# Chess_MOD.net
KiCad netlist of a schematic drawn in EAGLE
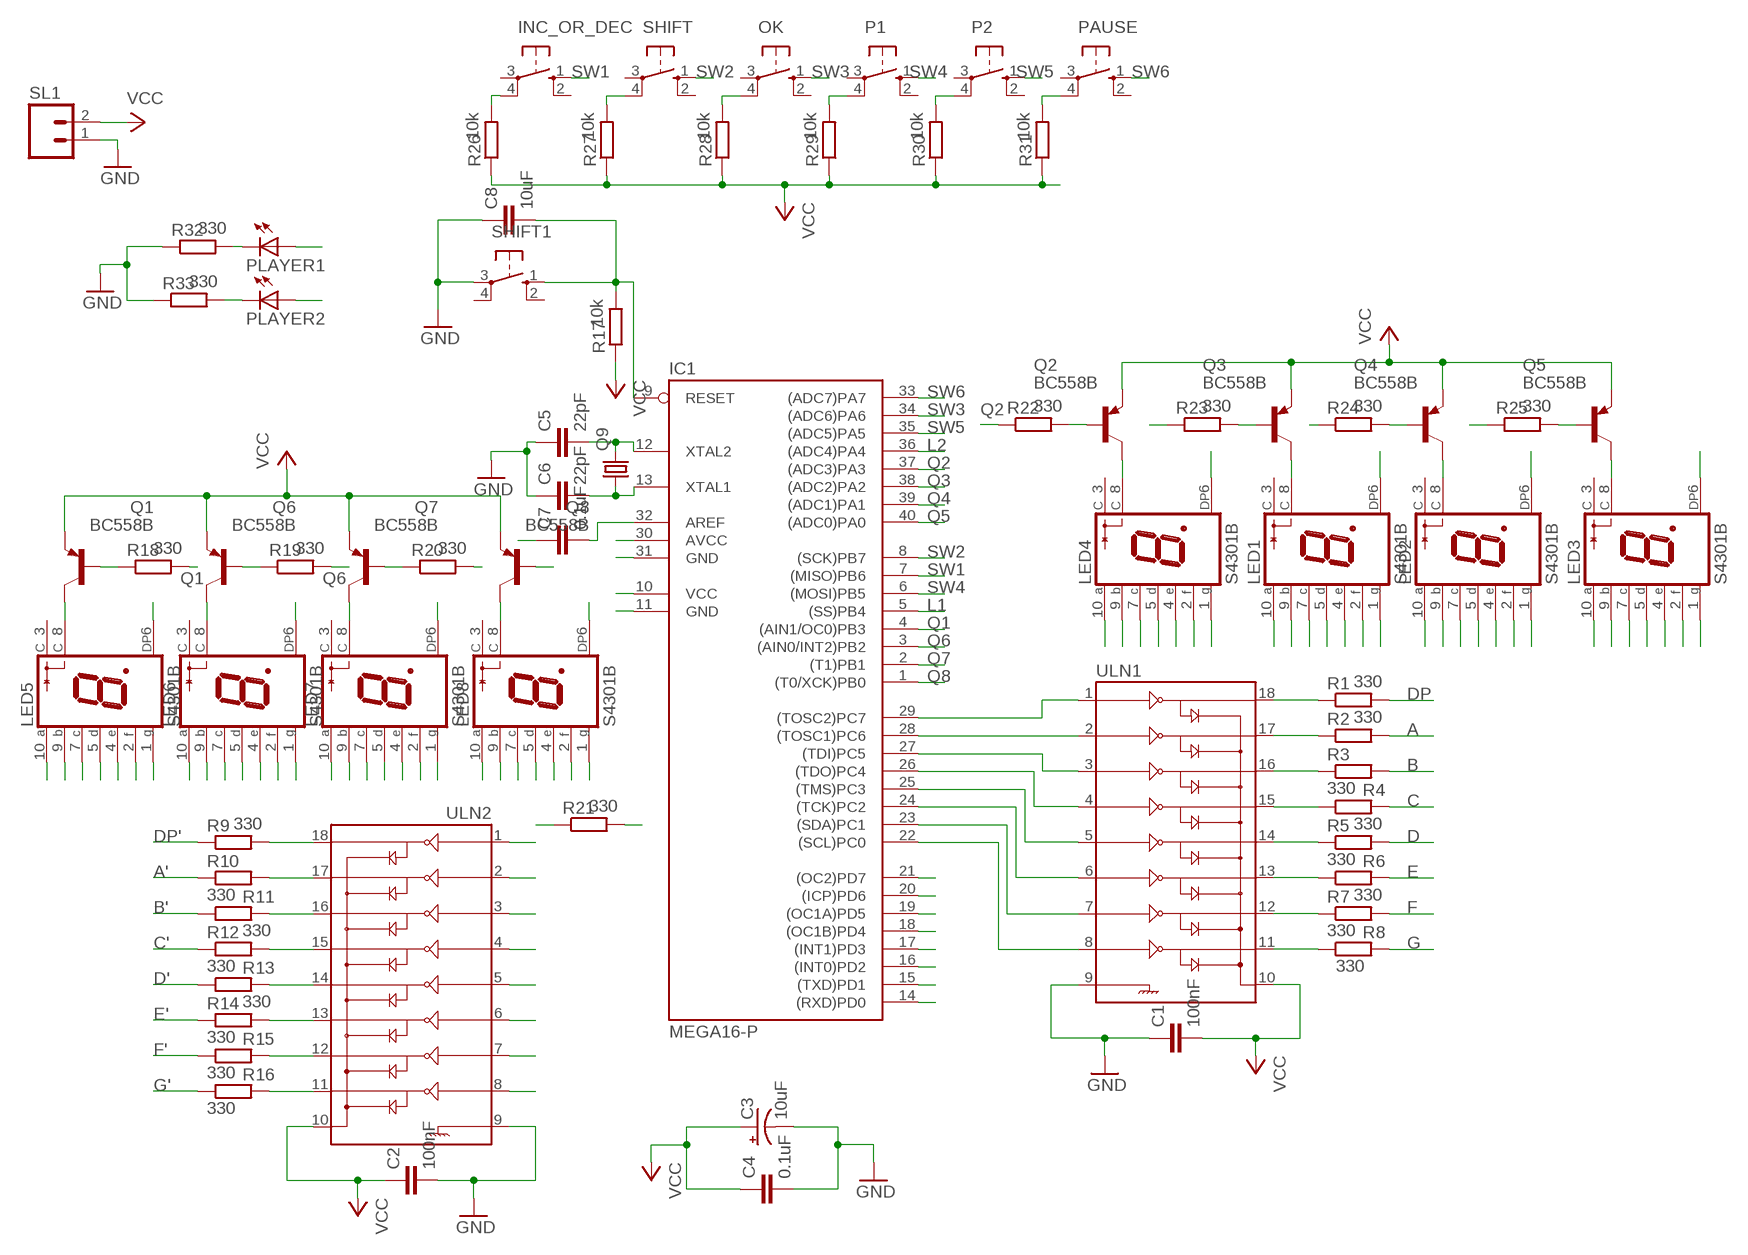
[diagram p0: schematic, sheet 1]

(export (version "E")
  (design (tool "Eeschema 10.0.6"))
  (components
    (comp (ref "C1")
      (value "100nF")
      (footprint "eagle-import:C025-024X044")
      (libsource (lib "eagle-import") (part "C-EU025-024X044"))
    )
    (comp (ref "C2")
      (value "100nF")
      (footprint "eagle-import:C025-024X044")
      (libsource (lib "eagle-import") (part "C-EU025-024X044"))
    )
    (comp (ref "C3")
      (value "10uF")
      (footprint "eagle-import:E2,5-7")
      (libsource (lib "eagle-import") (part "CPOL-USE2.5-7"))
    )
    (comp (ref "C4")
      (value "0.1uF")
      (footprint "eagle-import:C025-024X044")
      (libsource (lib "eagle-import") (part "C-EU025-024X044"))
    )
    (comp (ref "C5")
      (value "22pF")
      (footprint "eagle-import:C025-024X044")
      (libsource (lib "eagle-import") (part "C-EU025-024X044"))
    )
    (comp (ref "C6")
      (value "22pF")
      (footprint "eagle-import:C025-024X044")
      (libsource (lib "eagle-import") (part "C-EU025-024X044"))
    )
    (comp (ref "C7")
      (value "0.1uF")
      (footprint "eagle-import:C025-024X044")
      (libsource (lib "eagle-import") (part "C-EU025-024X044"))
    )
    (comp (ref "C8")
      (value "10uF")
      (footprint "eagle-import:C025-024X044")
      (libsource (lib "eagle-import") (part "C-EU025-024X044"))
    )
    (comp (ref "IC1")
      (value "MEGA16-P")
      (footprint "eagle-import:DIL40")
      (fields (field (name "MPN") "ATMEGA16-16PU"))
      (libsource (lib "eagle-import") (part "MEGA16-P"))
    )
    (comp (ref "INC_OR_DEC")
      (value "10-XX")
      (footprint "eagle-import:B3F-10XX")
      (fields (field (name "MPN") "B3F-1000"))
      (libsource (lib "eagle-import") (part "10-XX"))
    )
    (comp (ref "LED1")
      (value "S4301B")
      (footprint "eagle-import:S4301B")
      (libsource (lib "eagle-import") (part "S4301B"))
    )
    (comp (ref "LED2")
      (value "S4301B")
      (footprint "eagle-import:S4301B")
      (libsource (lib "eagle-import") (part "S4301B"))
    )
    (comp (ref "LED3")
      (value "S4301B")
      (footprint "eagle-import:S4301B")
      (libsource (lib "eagle-import") (part "S4301B"))
    )
    (comp (ref "LED4")
      (value "S4301B")
      (footprint "eagle-import:S4301B")
      (libsource (lib "eagle-import") (part "S4301B"))
    )
    (comp (ref "LED5")
      (value "S4301B")
      (footprint "eagle-import:S4301B")
      (libsource (lib "eagle-import") (part "S4301B"))
    )
    (comp (ref "LED6")
      (value "S4301B")
      (footprint "eagle-import:S4301B")
      (libsource (lib "eagle-import") (part "S4301B"))
    )
    (comp (ref "LED7")
      (value "S4301B")
      (footprint "eagle-import:S4301B")
      (libsource (lib "eagle-import") (part "S4301B"))
    )
    (comp (ref "LED8")
      (value "S4301B")
      (footprint "eagle-import:S4301B")
      (libsource (lib "eagle-import") (part "S4301B"))
    )
    (comp (ref "OK")
      (value "10-XX")
      (footprint "eagle-import:B3F-10XX")
      (fields (field (name "MPN") "B3F-1000"))
      (libsource (lib "eagle-import") (part "10-XX"))
    )
    (comp (ref "P1")
      (value "10-XX")
      (footprint "eagle-import:B3F-10XX")
      (fields (field (name "MPN") "B3F-1000"))
      (libsource (lib "eagle-import") (part "10-XX"))
    )
    (comp (ref "P2")
      (value "10-XX")
      (footprint "eagle-import:B3F-10XX")
      (fields (field (name "MPN") "B3F-1000"))
      (libsource (lib "eagle-import") (part "10-XX"))
    )
    (comp (ref "PAUSE")
      (value "10-XX")
      (footprint "eagle-import:B3F-10XX")
      (fields (field (name "MPN") "B3F-1000"))
      (libsource (lib "eagle-import") (part "10-XX"))
    )
    (comp (ref "PLAYER1")
      (value "LED5MM")
      (footprint "eagle-import:LED5MM")
      (libsource (lib "eagle-import") (part "LED5MM"))
    )
    (comp (ref "PLAYER2")
      (value "LED5MM")
      (footprint "eagle-import:LED5MM")
      (libsource (lib "eagle-import") (part "LED5MM"))
    )
    (comp (ref "Q1")
      (value "BC558B")
      (footprint "eagle-import:TO92-EBC")
      (libsource (lib "eagle-import") (part "BC558B"))
    )
    (comp (ref "Q2")
      (value "BC558B")
      (footprint "eagle-import:TO92-EBC")
      (libsource (lib "eagle-import") (part "BC558B"))
    )
    (comp (ref "Q3")
      (value "BC558B")
      (footprint "eagle-import:TO92-EBC")
      (libsource (lib "eagle-import") (part "BC558B"))
    )
    (comp (ref "Q4")
      (value "BC558B")
      (footprint "eagle-import:TO92-EBC")
      (libsource (lib "eagle-import") (part "BC558B"))
    )
    (comp (ref "Q5")
      (value "BC558B")
      (footprint "eagle-import:TO92-EBC")
      (libsource (lib "eagle-import") (part "BC558B"))
    )
    (comp (ref "Q6")
      (value "BC558B")
      (footprint "eagle-import:TO92-EBC")
      (libsource (lib "eagle-import") (part "BC558B"))
    )
    (comp (ref "Q7")
      (value "BC558B")
      (footprint "eagle-import:TO92-EBC")
      (libsource (lib "eagle-import") (part "BC558B"))
    )
    (comp (ref "Q8")
      (value "BC558B")
      (footprint "eagle-import:TO92-EBC")
      (libsource (lib "eagle-import") (part "BC558B"))
    )
    (comp (ref "Q9")
      (value "CRYSTALHC49US")
      (footprint "eagle-import:HC49US")
      (libsource (lib "eagle-import") (part "CRYSTALHC49US"))
    )
    (comp (ref "R1")
      (value "330")
      (footprint "eagle-import:0204_7")
      (libsource (lib "eagle-import") (part "R-EU_0204/7"))
    )
    (comp (ref "R2")
      (value "330")
      (footprint "eagle-import:0204_7")
      (libsource (lib "eagle-import") (part "R-EU_0204/7"))
    )
    (comp (ref "R3")
      (value "330")
      (footprint "eagle-import:0204_7")
      (libsource (lib "eagle-import") (part "R-EU_0204/7"))
    )
    (comp (ref "R4")
      (value "330")
      (footprint "eagle-import:0204_7")
      (libsource (lib "eagle-import") (part "R-EU_0204/7"))
    )
    (comp (ref "R5")
      (value "330")
      (footprint "eagle-import:0204_7")
      (libsource (lib "eagle-import") (part "R-EU_0204/7"))
    )
    (comp (ref "R6")
      (value "330")
      (footprint "eagle-import:0204_7")
      (libsource (lib "eagle-import") (part "R-EU_0204/7"))
    )
    (comp (ref "R7")
      (value "330")
      (footprint "eagle-import:0204_7")
      (libsource (lib "eagle-import") (part "R-EU_0204/7"))
    )
    (comp (ref "R8")
      (value "330")
      (footprint "eagle-import:0204_7")
      (libsource (lib "eagle-import") (part "R-EU_0204/7"))
    )
    (comp (ref "R9")
      (value "330")
      (footprint "eagle-import:0204_7")
      (libsource (lib "eagle-import") (part "R-EU_0204/7"))
    )
    (comp (ref "R10")
      (value "330")
      (footprint "eagle-import:0204_7")
      (libsource (lib "eagle-import") (part "R-EU_0204/7"))
    )
    (comp (ref "R11")
      (value "330")
      (footprint "eagle-import:0204_7")
      (libsource (lib "eagle-import") (part "R-EU_0204/7"))
    )
    (comp (ref "R12")
      (value "330")
      (footprint "eagle-import:0204_7")
      (libsource (lib "eagle-import") (part "R-EU_0204/7"))
    )
    (comp (ref "R13")
      (value "330")
      (footprint "eagle-import:0204_7")
      (libsource (lib "eagle-import") (part "R-EU_0204/7"))
    )
    (comp (ref "R14")
      (value "330")
      (footprint "eagle-import:0204_7")
      (libsource (lib "eagle-import") (part "R-EU_0204/7"))
    )
    (comp (ref "R15")
      (value "330")
      (footprint "eagle-import:0204_7")
      (libsource (lib "eagle-import") (part "R-EU_0204/7"))
    )
    (comp (ref "R16")
      (value "330")
      (footprint "eagle-import:0204_7")
      (libsource (lib "eagle-import") (part "R-EU_0204/7"))
    )
    (comp (ref "R17")
      (value "10k")
      (footprint "eagle-import:0204_7")
      (libsource (lib "eagle-import") (part "R-EU_0204/7"))
    )
    (comp (ref "R18")
      (value "330")
      (footprint "eagle-import:0204_7")
      (libsource (lib "eagle-import") (part "R-EU_0204/7"))
    )
    (comp (ref "R19")
      (value "330")
      (footprint "eagle-import:0204_7")
      (libsource (lib "eagle-import") (part "R-EU_0204/7"))
    )
    (comp (ref "R20")
      (value "330")
      (footprint "eagle-import:0204_7")
      (libsource (lib "eagle-import") (part "R-EU_0204/7"))
    )
    (comp (ref "R21")
      (value "330")
      (footprint "eagle-import:0204_7")
      (libsource (lib "eagle-import") (part "R-EU_0204/7"))
    )
    (comp (ref "R22")
      (value "330")
      (footprint "eagle-import:0204_7")
      (libsource (lib "eagle-import") (part "R-EU_0204/7"))
    )
    (comp (ref "R23")
      (value "330")
      (footprint "eagle-import:0204_7")
      (libsource (lib "eagle-import") (part "R-EU_0204/7"))
    )
    (comp (ref "R24")
      (value "330")
      (footprint "eagle-import:0204_7")
      (libsource (lib "eagle-import") (part "R-EU_0204/7"))
    )
    (comp (ref "R25")
      (value "330")
      (footprint "eagle-import:0204_7")
      (libsource (lib "eagle-import") (part "R-EU_0204/7"))
    )
    (comp (ref "R26")
      (value "10k")
      (footprint "eagle-import:0204_7")
      (libsource (lib "eagle-import") (part "R-EU_0204/7"))
    )
    (comp (ref "R27")
      (value "10k")
      (footprint "eagle-import:0204_7")
      (libsource (lib "eagle-import") (part "R-EU_0204/7"))
    )
    (comp (ref "R28")
      (value "10k")
      (footprint "eagle-import:0204_7")
      (libsource (lib "eagle-import") (part "R-EU_0204/7"))
    )
    (comp (ref "R29")
      (value "10k")
      (footprint "eagle-import:0204_7")
      (libsource (lib "eagle-import") (part "R-EU_0204/7"))
    )
    (comp (ref "R30")
      (value "10k")
      (footprint "eagle-import:0204_7")
      (libsource (lib "eagle-import") (part "R-EU_0204/7"))
    )
    (comp (ref "R31")
      (value "10k")
      (footprint "eagle-import:0204_7")
      (libsource (lib "eagle-import") (part "R-EU_0204/7"))
    )
    (comp (ref "R32")
      (value "330")
      (footprint "eagle-import:0204_7")
      (libsource (lib "eagle-import") (part "R-EU_0204/7"))
    )
    (comp (ref "R33")
      (value "330")
      (footprint "eagle-import:0204_7")
      (libsource (lib "eagle-import") (part "R-EU_0204/7"))
    )
    (comp (ref "SHIFT")
      (value "10-XX")
      (footprint "eagle-import:B3F-10XX")
      (fields (field (name "MPN") "B3F-1000"))
      (libsource (lib "eagle-import") (part "10-XX"))
    )
    (comp (ref "SHIFT1")
      (value "10-XX")
      (footprint "eagle-import:B3F-10XX")
      (fields (field (name "MPN") "B3F-1000"))
      (libsource (lib "eagle-import") (part "10-XX"))
    )
    (comp (ref "SL1")
      (value "M02")
      (footprint "eagle-import:02P")
      (libsource (lib "eagle-import") (part "M02"))
    )
    (comp (ref "ULN1")
      (value "ULN2803DIP")
      (footprint "eagle-import:DIL18")
      (libsource (lib "eagle-import") (part "ULN2803DIP"))
    )
    (comp (ref "ULN2")
      (value "ULN2803DIP")
      (footprint "eagle-import:DIL18")
      (libsource (lib "eagle-import") (part "ULN2803DIP"))
    )
  )
  (nets
    (net (code "1") (name "/1") (class "Default")
      (node (ref "IC1") (pin "21") (pinfunction "(OC2)PD7_21") (pintype "bidirectional"))
      (node (ref "ULN2") (pin "1") (pinfunction "1_1") (pintype "bidirectional"))
    )
    (net (code "2") (name "/2") (class "Default")
      (node (ref "IC1") (pin "20") (pinfunction "(ICP)PD6_20") (pintype "bidirectional"))
      (node (ref "ULN2") (pin "2") (pinfunction "2_2") (pintype "bidirectional"))
    )
    (net (code "3") (name "/3") (class "Default")
      (node (ref "IC1") (pin "19") (pinfunction "(OC1A)PD5_19") (pintype "bidirectional"))
      (node (ref "ULN2") (pin "3") (pinfunction "3_3") (pintype "bidirectional"))
    )
    (net (code "4") (name "/4") (class "Default")
      (node (ref "IC1") (pin "18") (pinfunction "(OC1B)PD4_18") (pintype "bidirectional"))
      (node (ref "ULN2") (pin "4") (pinfunction "4_4") (pintype "bidirectional"))
    )
    (net (code "5") (name "/5") (class "Default")
      (node (ref "IC1") (pin "17") (pinfunction "(INT1)PD3_17") (pintype "bidirectional"))
      (node (ref "ULN2") (pin "5") (pinfunction "5_5") (pintype "bidirectional"))
    )
    (net (code "6") (name "/6") (class "Default")
      (node (ref "IC1") (pin "16") (pinfunction "(INT0)PD2_16") (pintype "bidirectional"))
      (node (ref "ULN2") (pin "6") (pinfunction "6_6") (pintype "bidirectional"))
    )
    (net (code "7") (name "/7") (class "Default")
      (node (ref "IC1") (pin "15") (pinfunction "(TXD)PD1_15") (pintype "bidirectional"))
      (node (ref "ULN2") (pin "7") (pinfunction "7_7") (pintype "bidirectional"))
    )
    (net (code "8") (name "/8") (class "Default")
      (node (ref "IC1") (pin "14") (pinfunction "(RXD)PD0_14") (pintype "bidirectional"))
      (node (ref "ULN2") (pin "8") (pinfunction "8_8") (pintype "bidirectional"))
    )
    (net (code "9") (name "/A") (class "Default")
      (node (ref "LED1") (pin "10") (pinfunction "A_10") (pintype "passive"))
      (node (ref "LED2") (pin "10") (pinfunction "A_10") (pintype "passive"))
      (node (ref "LED3") (pin "10") (pinfunction "A_10") (pintype "passive"))
      (node (ref "LED4") (pin "10") (pinfunction "A_10") (pintype "passive"))
      (node (ref "R2") (pin "2") (pinfunction "2_2") (pintype "passive"))
    )
    (net (code "10") (name "/A'") (class "Default")
      (node (ref "LED5") (pin "10") (pinfunction "A_10") (pintype "passive"))
      (node (ref "LED6") (pin "10") (pinfunction "A_10") (pintype "passive"))
      (node (ref "LED7") (pin "10") (pinfunction "A_10") (pintype "passive"))
      (node (ref "LED8") (pin "10") (pinfunction "A_10") (pintype "passive"))
      (node (ref "R10") (pin "1") (pinfunction "1_1") (pintype "passive"))
    )
    (net (code "11") (name "/B") (class "Default")
      (node (ref "LED1") (pin "9") (pinfunction "B_9") (pintype "passive"))
      (node (ref "LED2") (pin "9") (pinfunction "B_9") (pintype "passive"))
      (node (ref "LED3") (pin "9") (pinfunction "B_9") (pintype "passive"))
      (node (ref "LED4") (pin "9") (pinfunction "B_9") (pintype "passive"))
      (node (ref "R3") (pin "2") (pinfunction "2_2") (pintype "passive"))
    )
    (net (code "12") (name "/B'") (class "Default")
      (node (ref "LED5") (pin "9") (pinfunction "B_9") (pintype "passive"))
      (node (ref "LED6") (pin "9") (pinfunction "B_9") (pintype "passive"))
      (node (ref "LED7") (pin "9") (pinfunction "B_9") (pintype "passive"))
      (node (ref "LED8") (pin "9") (pinfunction "B_9") (pintype "passive"))
      (node (ref "R11") (pin "1") (pinfunction "1_1") (pintype "passive"))
    )
    (net (code "13") (name "/C") (class "Default")
      (node (ref "LED1") (pin "7") (pinfunction "C_7") (pintype "passive"))
      (node (ref "LED2") (pin "7") (pinfunction "C_7") (pintype "passive"))
      (node (ref "LED3") (pin "7") (pinfunction "C_7") (pintype "passive"))
      (node (ref "LED4") (pin "7") (pinfunction "C_7") (pintype "passive"))
      (node (ref "R4") (pin "2") (pinfunction "2_2") (pintype "passive"))
    )
    (net (code "14") (name "/C'") (class "Default")
      (node (ref "LED5") (pin "7") (pinfunction "C_7") (pintype "passive"))
      (node (ref "LED6") (pin "7") (pinfunction "C_7") (pintype "passive"))
      (node (ref "LED7") (pin "7") (pinfunction "C_7") (pintype "passive"))
      (node (ref "LED8") (pin "7") (pinfunction "C_7") (pintype "passive"))
      (node (ref "R12") (pin "1") (pinfunction "1_1") (pintype "passive"))
    )
    (net (code "15") (name "/D") (class "Default")
      (node (ref "LED1") (pin "5") (pinfunction "D_5") (pintype "passive"))
      (node (ref "LED2") (pin "5") (pinfunction "D_5") (pintype "passive"))
      (node (ref "LED3") (pin "5") (pinfunction "D_5") (pintype "passive"))
      (node (ref "LED4") (pin "5") (pinfunction "D_5") (pintype "passive"))
      (node (ref "R5") (pin "2") (pinfunction "2_2") (pintype "passive"))
    )
    (net (code "16") (name "/D'") (class "Default")
      (node (ref "LED5") (pin "5") (pinfunction "D_5") (pintype "passive"))
      (node (ref "LED6") (pin "5") (pinfunction "D_5") (pintype "passive"))
      (node (ref "LED7") (pin "5") (pinfunction "D_5") (pintype "passive"))
      (node (ref "LED8") (pin "5") (pinfunction "D_5") (pintype "passive"))
      (node (ref "R13") (pin "1") (pinfunction "1_1") (pintype "passive"))
    )
    (net (code "17") (name "/DP") (class "Default")
      (node (ref "LED1") (pin "6") (pinfunction "DP_6") (pintype "passive"))
      (node (ref "LED2") (pin "6") (pinfunction "DP_6") (pintype "passive"))
      (node (ref "LED3") (pin "6") (pinfunction "DP_6") (pintype "passive"))
      (node (ref "LED4") (pin "6") (pinfunction "DP_6") (pintype "passive"))
      (node (ref "R1") (pin "2") (pinfunction "2_2") (pintype "passive"))
    )
    (net (code "18") (name "/DP'") (class "Default")
      (node (ref "LED5") (pin "6") (pinfunction "DP_6") (pintype "passive"))
      (node (ref "LED6") (pin "6") (pinfunction "DP_6") (pintype "passive"))
      (node (ref "LED7") (pin "6") (pinfunction "DP_6") (pintype "passive"))
      (node (ref "LED8") (pin "6") (pinfunction "DP_6") (pintype "passive"))
      (node (ref "R9") (pin "1") (pinfunction "1_1") (pintype "passive"))
    )
    (net (code "19") (name "/E") (class "Default")
      (node (ref "LED2") (pin "4") (pinfunction "E_4") (pintype "passive"))
      (node (ref "LED3") (pin "4") (pinfunction "E_4") (pintype "passive"))
      (node (ref "LED4") (pin "4") (pinfunction "E_4") (pintype "passive"))
      (node (ref "R6") (pin "2") (pinfunction "2_2") (pintype "passive"))
    )
    (net (code "20") (name "/E'") (class "Default")
      (node (ref "LED5") (pin "4") (pinfunction "E_4") (pintype "passive"))
      (node (ref "LED6") (pin "4") (pinfunction "E_4") (pintype "passive"))
      (node (ref "LED7") (pin "4") (pinfunction "E_4") (pintype "passive"))
      (node (ref "LED8") (pin "4") (pinfunction "E_4") (pintype "passive"))
      (node (ref "R14") (pin "1") (pinfunction "1_1") (pintype "passive"))
    )
    (net (code "21") (name "/F") (class "Default")
      (node (ref "LED1") (pin "2") (pinfunction "F_2") (pintype "passive"))
      (node (ref "LED2") (pin "2") (pinfunction "F_2") (pintype "passive"))
      (node (ref "LED3") (pin "2") (pinfunction "F_2") (pintype "passive"))
      (node (ref "LED4") (pin "2") (pinfunction "F_2") (pintype "passive"))
      (node (ref "R7") (pin "2") (pinfunction "2_2") (pintype "passive"))
    )
    (net (code "22") (name "/F'") (class "Default")
      (node (ref "LED5") (pin "2") (pinfunction "F_2") (pintype "passive"))
      (node (ref "LED6") (pin "2") (pinfunction "F_2") (pintype "passive"))
      (node (ref "LED7") (pin "2") (pinfunction "F_2") (pintype "passive"))
      (node (ref "LED8") (pin "2") (pinfunction "F_2") (pintype "passive"))
      (node (ref "R15") (pin "1") (pinfunction "1_1") (pintype "passive"))
    )
    (net (code "23") (name "/G") (class "Default")
      (node (ref "LED1") (pin "1") (pinfunction "G_1") (pintype "passive"))
      (node (ref "LED2") (pin "1") (pinfunction "G_1") (pintype "passive"))
      (node (ref "LED3") (pin "1") (pinfunction "G_1") (pintype "passive"))
      (node (ref "LED4") (pin "1") (pinfunction "G_1") (pintype "passive"))
      (node (ref "R8") (pin "2") (pinfunction "2_2") (pintype "passive"))
    )
    (net (code "24") (name "/G'") (class "Default")
      (node (ref "LED5") (pin "1") (pinfunction "G_1") (pintype "passive"))
      (node (ref "LED6") (pin "1") (pinfunction "G_1") (pintype "passive"))
      (node (ref "LED7") (pin "1") (pinfunction "G_1") (pintype "passive"))
      (node (ref "LED8") (pin "1") (pinfunction "G_1") (pintype "passive"))
      (node (ref "R16") (pin "1") (pinfunction "1_1") (pintype "passive"))
    )
    (net (code "25") (name "/L1") (class "Default")
      (node (ref "IC1") (pin "5") (pinfunction "(SS)PB4_5") (pintype "bidirectional"))
      (node (ref "PLAYER1") (pin "A") (pinfunction "A_A") (pintype "passive"))
    )
    (net (code "26") (name "/L2") (class "Default")
      (node (ref "IC1") (pin "36") (pinfunction "(ADC4)PA4_36") (pintype "bidirectional"))
      (node (ref "PLAYER2") (pin "A") (pinfunction "A_A") (pintype "passive"))
    )
    (net (code "27") (name "/Q1") (class "Default")
      (node (ref "IC1") (pin "4") (pinfunction "(AIN1/OC0)PB3_4") (pintype "bidirectional"))
      (node (ref "R18") (pin "2") (pinfunction "2_2") (pintype "passive"))
    )
    (net (code "28") (name "/Q2") (class "Default")
      (node (ref "IC1") (pin "37") (pinfunction "(ADC3)PA3_37") (pintype "bidirectional"))
      (node (ref "R22") (pin "1") (pinfunction "1_1") (pintype "passive"))
    )
    (net (code "29") (name "/Q3") (class "Default")
      (node (ref "IC1") (pin "38") (pinfunction "(ADC2)PA2_38") (pintype "bidirectional"))
      (node (ref "R23") (pin "1") (pinfunction "1_1") (pintype "passive"))
    )
    (net (code "30") (name "/Q4") (class "Default")
      (node (ref "IC1") (pin "39") (pinfunction "(ADC1)PA1_39") (pintype "bidirectional"))
      (node (ref "R24") (pin "1") (pinfunction "1_1") (pintype "passive"))
    )
    (net (code "31") (name "/Q5") (class "Default")
      (node (ref "IC1") (pin "40") (pinfunction "(ADC0)PA0_40") (pintype "bidirectional"))
      (node (ref "R25") (pin "1") (pinfunction "1_1") (pintype "passive"))
    )
    (net (code "32") (name "/Q6") (class "Default")
      (node (ref "IC1") (pin "3") (pinfunction "(AIN0/INT2)PB2_3") (pintype "bidirectional"))
      (node (ref "R19") (pin "2") (pinfunction "2_2") (pintype "passive"))
    )
    (net (code "33") (name "/Q7") (class "Default")
      (node (ref "IC1") (pin "2") (pinfunction "(T1)PB1_2") (pintype "bidirectional"))
      (node (ref "R20") (pin "2") (pinfunction "2_2") (pintype "passive"))
    )
    (net (code "34") (name "/Q8") (class "Default")
      (node (ref "IC1") (pin "1") (pinfunction "(T0/XCK)PB0_1") (pintype "bidirectional"))
      (node (ref "R21") (pin "2") (pinfunction "2_2") (pintype "passive"))
    )
    (net (code "35") (name "/SW1") (class "Default")
      (node (ref "IC1") (pin "7") (pinfunction "(MISO)PB6_7") (pintype "bidirectional"))
      (node (ref "INC_OR_DEC") (pin "1") (pinfunction "S_1") (pintype "passive"))
    )
    (net (code "36") (name "/SW2") (class "Default")
      (node (ref "IC1") (pin "8") (pinfunction "(SCK)PB7_8") (pintype "bidirectional"))
      (node (ref "SHIFT") (pin "1") (pinfunction "S_1") (pintype "passive"))
    )
    (net (code "37") (name "/SW3") (class "Default")
      (node (ref "IC1") (pin "34") (pinfunction "(ADC6)PA6_34") (pintype "bidirectional"))
      (node (ref "OK") (pin "1") (pinfunction "S_1") (pintype "passive"))
    )
    (net (code "38") (name "/SW4") (class "Default")
      (node (ref "IC1") (pin "6") (pinfunction "(MOSI)PB5_6") (pintype "bidirectional"))
      (node (ref "P1") (pin "1") (pinfunction "S_1") (pintype "passive"))
    )
    (net (code "39") (name "/SW5") (class "Default")
      (node (ref "IC1") (pin "35") (pinfunction "(ADC5)PA5_35") (pintype "bidirectional"))
      (node (ref "P2") (pin "1") (pinfunction "S_1") (pintype "passive"))
    )
    (net (code "40") (name "/SW6") (class "Default")
      (node (ref "IC1") (pin "33") (pinfunction "(ADC7)PA7_33") (pintype "bidirectional"))
      (node (ref "PAUSE") (pin "1") (pinfunction "S_1") (pintype "passive"))
    )
    (net (code "41") (name "/T1") (class "Default")
      (node (ref "Q8") (pin "B") (pinfunction "B_B") (pintype "passive"))
      (node (ref "R21") (pin "1") (pinfunction "1_1") (pintype "passive"))
    )
    (net (code "42") (name "GND") (class "Default")
      (node (ref "C1") (pin "1") (pinfunction "1_1") (pintype "passive"))
      (node (ref "C2") (pin "2") (pinfunction "2_2") (pintype "passive"))
      (node (ref "C3") (pin "-") (pinfunction "-_-") (pintype "passive"))
      (node (ref "C4") (pin "2") (pinfunction "2_2") (pintype "passive"))
      (node (ref "C5") (pin "1") (pinfunction "1_1") (pintype "passive"))
      (node (ref "C6") (pin "1") (pinfunction "1_1") (pintype "passive"))
      (node (ref "C8") (pin "1") (pinfunction "1_1") (pintype "passive"))
      (node (ref "IC1") (pin "11") (pinfunction "GND_11") (pintype "power_in"))
      (node (ref "IC1") (pin "31") (pinfunction "GND_31") (pintype "power_in"))
      (node (ref "R32") (pin "1") (pinfunction "1_1") (pintype "passive"))
      (node (ref "R33") (pin "1") (pinfunction "1_1") (pintype "passive"))
      (node (ref "SHIFT1") (pin "3") (pinfunction "P_3") (pintype "passive"))
      (node (ref "SL1") (pin "1") (pinfunction "1_1") (pintype "passive"))
      (node (ref "ULN1") (pin "9") (pinfunction "9_9") (pintype "bidirectional"))
      (node (ref "ULN2") (pin "9") (pinfunction "9_9") (pintype "bidirectional"))
    )
    (net (code "43") (name "Net-(IC1-(SCL)PC0)") (class "Default")
      (node (ref "IC1") (pin "22") (pinfunction "(SCL)PC0_22") (pintype "bidirectional"))
      (node (ref "ULN1") (pin "8") (pinfunction "8_8") (pintype "bidirectional"))
    )
    (net (code "44") (name "Net-(IC1-(SDA)PC1)") (class "Default")
      (node (ref "IC1") (pin "23") (pinfunction "(SDA)PC1_23") (pintype "bidirectional"))
      (node (ref "ULN1") (pin "7") (pinfunction "7_7") (pintype "bidirectional"))
    )
    (net (code "45") (name "Net-(IC1-(TCK)PC2)") (class "Default")
      (node (ref "IC1") (pin "24") (pinfunction "(TCK)PC2_24") (pintype "bidirectional"))
      (node (ref "ULN1") (pin "6") (pinfunction "6_6") (pintype "bidirectional"))
    )
    (net (code "46") (name "Net-(IC1-(TDI)PC5)") (class "Default")
      (node (ref "IC1") (pin "27") (pinfunction "(TDI)PC5_27") (pintype "bidirectional"))
      (node (ref "ULN1") (pin "3") (pinfunction "3_3") (pintype "bidirectional"))
    )
    (net (code "47") (name "Net-(IC1-(TDO)PC4)") (class "Default")
      (node (ref "IC1") (pin "26") (pinfunction "(TDO)PC4_26") (pintype "bidirectional"))
      (node (ref "ULN1") (pin "4") (pinfunction "4_4") (pintype "bidirectional"))
    )
    (net (code "48") (name "Net-(IC1-(TMS)PC3)") (class "Default")
      (node (ref "IC1") (pin "25") (pinfunction "(TMS)PC3_25") (pintype "bidirectional"))
      (node (ref "ULN1") (pin "5") (pinfunction "5_5") (pintype "bidirectional"))
    )
    (net (code "49") (name "Net-(IC1-(TOSC1)PC6)") (class "Default")
      (node (ref "IC1") (pin "28") (pinfunction "(TOSC1)PC6_28") (pintype "bidirectional"))
      (node (ref "ULN1") (pin "2") (pinfunction "2_2") (pintype "bidirectional"))
    )
    (net (code "50") (name "Net-(IC1-(TOSC2)PC7)") (class "Default")
      (node (ref "IC1") (pin "29") (pinfunction "(TOSC2)PC7_29") (pintype "bidirectional"))
      (node (ref "ULN1") (pin "1") (pinfunction "1_1") (pintype "bidirectional"))
    )
    (net (code "51") (name "Net-(IC1-AREF)") (class "Default")
      (node (ref "C7") (pin "2") (pinfunction "2_2") (pintype "passive"))
      (node (ref "IC1") (pin "32") (pinfunction "AREF_32") (pintype "passive"))
    )
    (net (code "52") (name "Net-(IC1-RESET)") (class "Default")
      (node (ref "C8") (pin "2") (pinfunction "2_2") (pintype "passive"))
      (node (ref "IC1") (pin "9") (pinfunction "RESET_9") (pintype "input"))
      (node (ref "R17") (pin "2") (pinfunction "2_2") (pintype "passive"))
      (node (ref "SHIFT1") (pin "1") (pinfunction "S_1") (pintype "passive"))
    )
    (net (code "53") (name "Net-(IC1-XTAL1)") (class "Default")
      (node (ref "C6") (pin "2") (pinfunction "2_2") (pintype "passive"))
      (node (ref "IC1") (pin "13") (pinfunction "XTAL1_13") (pintype "bidirectional"))
      (node (ref "Q9") (pin "1") (pinfunction "1_1") (pintype "passive"))
    )
    (net (code "54") (name "Net-(IC1-XTAL2)") (class "Default")
      (node (ref "C5") (pin "2") (pinfunction "2_2") (pintype "passive"))
      (node (ref "IC1") (pin "12") (pinfunction "XTAL2_12") (pintype "bidirectional"))
      (node (ref "Q9") (pin "2") (pinfunction "2_2") (pintype "passive"))
    )
    (net (code "55") (name "Net-(INC_OR_DEC-P1)") (class "Default")
      (node (ref "INC_OR_DEC") (pin "4") (pinfunction "P1_4") (pintype "passive"))
      (node (ref "R26") (pin "2") (pinfunction "2_2") (pintype "passive"))
    )
    (net (code "56") (name "Net-(LED1-C-Pad8)") (class "Default")
      (node (ref "LED1") (pin "8") (pinfunction "C_8") (pintype "passive"))
      (node (ref "Q3") (pin "C") (pinfunction "C_C") (pintype "passive"))
    )
    (net (code "57") (name "Net-(LED2-C-Pad8)") (class "Default")
      (node (ref "LED2") (pin "8") (pinfunction "C_8") (pintype "passive"))
      (node (ref "Q4") (pin "C") (pinfunction "C_C") (pintype "passive"))
    )
    (net (code "58") (name "Net-(LED3-C-Pad8)") (class "Default")
      (node (ref "LED3") (pin "8") (pinfunction "C_8") (pintype "passive"))
      (node (ref "Q5") (pin "C") (pinfunction "C_C") (pintype "passive"))
    )
    (net (code "59") (name "Net-(LED4-C-Pad8)") (class "Default")
      (node (ref "LED4") (pin "8") (pinfunction "C_8") (pintype "passive"))
      (node (ref "Q2") (pin "C") (pinfunction "C_C") (pintype "passive"))
    )
    (net (code "60") (name "Net-(LED5-C-Pad8)") (class "Default")
      (node (ref "LED5") (pin "8") (pinfunction "C_8") (pintype "passive"))
      (node (ref "Q1") (pin "C") (pinfunction "C_C") (pintype "passive"))
    )
    (net (code "61") (name "Net-(LED6-C-Pad8)") (class "Default")
      (node (ref "LED6") (pin "8") (pinfunction "C_8") (pintype "passive"))
      (node (ref "Q6") (pin "C") (pinfunction "C_C") (pintype "passive"))
    )
    (net (code "62") (name "Net-(LED7-C-Pad8)") (class "Default")
      (node (ref "LED7") (pin "8") (pinfunction "C_8") (pintype "passive"))
      (node (ref "Q7") (pin "C") (pinfunction "C_C") (pintype "passive"))
    )
    (net (code "63") (name "Net-(LED8-C-Pad8)") (class "Default")
      (node (ref "LED8") (pin "8") (pinfunction "C_8") (pintype "passive"))
      (node (ref "Q8") (pin "C") (pinfunction "C_C") (pintype "passive"))
    )
    (net (code "64") (name "Net-(OK-P1)") (class "Default")
      (node (ref "OK") (pin "4") (pinfunction "P1_4") (pintype "passive"))
      (node (ref "R28") (pin "2") (pinfunction "2_2") (pintype "passive"))
    )
    (net (code "65") (name "Net-(P1-P1)") (class "Default")
      (node (ref "P1") (pin "4") (pinfunction "P1_4") (pintype "passive"))
      (node (ref "R29") (pin "2") (pinfunction "2_2") (pintype "passive"))
    )
    (net (code "66") (name "Net-(P2-P1)") (class "Default")
      (node (ref "P2") (pin "4") (pinfunction "P1_4") (pintype "passive"))
      (node (ref "R30") (pin "2") (pinfunction "2_2") (pintype "passive"))
    )
    (net (code "67") (name "Net-(PAUSE-P1)") (class "Default")
      (node (ref "PAUSE") (pin "4") (pinfunction "P1_4") (pintype "passive"))
      (node (ref "R31") (pin "2") (pinfunction "2_2") (pintype "passive"))
    )
    (net (code "68") (name "Net-(PLAYER1-C)") (class "Default")
      (node (ref "PLAYER1") (pin "K") (pinfunction "C_K") (pintype "passive"))
      (node (ref "R32") (pin "2") (pinfunction "2_2") (pintype "passive"))
    )
    (net (code "69") (name "Net-(PLAYER2-C)") (class "Default")
      (node (ref "PLAYER2") (pin "K") (pinfunction "C_K") (pintype "passive"))
      (node (ref "R33") (pin "2") (pinfunction "2_2") (pintype "passive"))
    )
    (net (code "70") (name "Net-(Q1-PadB)") (class "Default")
      (node (ref "Q1") (pin "B") (pinfunction "B_B") (pintype "passive"))
      (node (ref "R18") (pin "1") (pinfunction "1_1") (pintype "passive"))
    )
    (net (code "71") (name "Net-(Q2-PadB)") (class "Default")
      (node (ref "Q2") (pin "B") (pinfunction "B_B") (pintype "passive"))
      (node (ref "R22") (pin "2") (pinfunction "2_2") (pintype "passive"))
    )
    (net (code "72") (name "Net-(Q3-PadB)") (class "Default")
      (node (ref "Q3") (pin "B") (pinfunction "B_B") (pintype "passive"))
      (node (ref "R23") (pin "2") (pinfunction "2_2") (pintype "passive"))
    )
    (net (code "73") (name "Net-(Q4-PadB)") (class "Default")
      (node (ref "Q4") (pin "B") (pinfunction "B_B") (pintype "passive"))
      (node (ref "R24") (pin "2") (pinfunction "2_2") (pintype "passive"))
    )
    (net (code "74") (name "Net-(Q5-PadB)") (class "Default")
      (node (ref "Q5") (pin "B") (pinfunction "B_B") (pintype "passive"))
      (node (ref "R25") (pin "2") (pinfunction "2_2") (pintype "passive"))
    )
    (net (code "75") (name "Net-(Q6-PadB)") (class "Default")
      (node (ref "Q6") (pin "B") (pinfunction "B_B") (pintype "passive"))
      (node (ref "R19") (pin "1") (pinfunction "1_1") (pintype "passive"))
    )
    (net (code "76") (name "Net-(Q7-PadB)") (class "Default")
      (node (ref "Q7") (pin "B") (pinfunction "B_B") (pintype "passive"))
      (node (ref "R20") (pin "1") (pinfunction "1_1") (pintype "passive"))
    )
    (net (code "77") (name "Net-(R1-Pad1)") (class "Default")
      (node (ref "R1") (pin "1") (pinfunction "1_1") (pintype "passive"))
      (node (ref "ULN1") (pin "18") (pinfunction "18_18") (pintype "bidirectional"))
    )
    (net (code "78") (name "Net-(R2-Pad1)") (class "Default")
      (node (ref "R2") (pin "1") (pinfunction "1_1") (pintype "passive"))
      (node (ref "ULN1") (pin "17") (pinfunction "17_17") (pintype "bidirectional"))
    )
    (net (code "79") (name "Net-(R3-Pad1)") (class "Default")
      (node (ref "R3") (pin "1") (pinfunction "1_1") (pintype "passive"))
      (node (ref "ULN1") (pin "16") (pinfunction "16_16") (pintype "bidirectional"))
    )
    (net (code "80") (name "Net-(R4-Pad1)") (class "Default")
      (node (ref "R4") (pin "1") (pinfunction "1_1") (pintype "passive"))
      (node (ref "ULN1") (pin "15") (pinfunction "15_15") (pintype "bidirectional"))
    )
    (net (code "81") (name "Net-(R5-Pad1)") (class "Default")
      (node (ref "R5") (pin "1") (pinfunction "1_1") (pintype "passive"))
      (node (ref "ULN1") (pin "14") (pinfunction "14_14") (pintype "bidirectional"))
    )
    (net (code "82") (name "Net-(R6-Pad1)") (class "Default")
      (node (ref "R6") (pin "1") (pinfunction "1_1") (pintype "passive"))
      (node (ref "ULN1") (pin "13") (pinfunction "13_13") (pintype "bidirectional"))
    )
    (net (code "83") (name "Net-(R7-Pad1)") (class "Default")
      (node (ref "R7") (pin "1") (pinfunction "1_1") (pintype "passive"))
      (node (ref "ULN1") (pin "12") (pinfunction "12_12") (pintype "bidirectional"))
    )
    (net (code "84") (name "Net-(R8-Pad1)") (class "Default")
      (node (ref "R8") (pin "1") (pinfunction "1_1") (pintype "passive"))
      (node (ref "ULN1") (pin "11") (pinfunction "11_11") (pintype "bidirectional"))
    )
    (net (code "85") (name "Net-(R9-Pad2)") (class "Default")
      (node (ref "R9") (pin "2") (pinfunction "2_2") (pintype "passive"))
      (node (ref "ULN2") (pin "18") (pinfunction "18_18") (pintype "bidirectional"))
    )
    (net (code "86") (name "Net-(R10-Pad2)") (class "Default")
      (node (ref "R10") (pin "2") (pinfunction "2_2") (pintype "passive"))
      (node (ref "ULN2") (pin "17") (pinfunction "17_17") (pintype "bidirectional"))
    )
    (net (code "87") (name "Net-(R11-Pad2)") (class "Default")
      (node (ref "R11") (pin "2") (pinfunction "2_2") (pintype "passive"))
      (node (ref "ULN2") (pin "16") (pinfunction "16_16") (pintype "bidirectional"))
    )
    (net (code "88") (name "Net-(R12-Pad2)") (class "Default")
      (node (ref "R12") (pin "2") (pinfunction "2_2") (pintype "passive"))
      (node (ref "ULN2") (pin "15") (pinfunction "15_15") (pintype "bidirectional"))
    )
    (net (code "89") (name "Net-(R13-Pad2)") (class "Default")
      (node (ref "R13") (pin "2") (pinfunction "2_2") (pintype "passive"))
      (node (ref "ULN2") (pin "14") (pinfunction "14_14") (pintype "bidirectional"))
    )
    (net (code "90") (name "Net-(R14-Pad2)") (class "Default")
      (node (ref "R14") (pin "2") (pinfunction "2_2") (pintype "passive"))
      (node (ref "ULN2") (pin "13") (pinfunction "13_13") (pintype "bidirectional"))
    )
    (net (code "91") (name "Net-(R15-Pad2)") (class "Default")
      (node (ref "R15") (pin "2") (pinfunction "2_2") (pintype "passive"))
      (node (ref "ULN2") (pin "12") (pinfunction "12_12") (pintype "bidirectional"))
    )
    (net (code "92") (name "Net-(R16-Pad2)") (class "Default")
      (node (ref "R16") (pin "2") (pinfunction "2_2") (pintype "passive"))
      (node (ref "ULN2") (pin "11") (pinfunction "11_11") (pintype "bidirectional"))
    )
    (net (code "93") (name "Net-(SHIFT-P1)") (class "Default")
      (node (ref "R27") (pin "2") (pinfunction "2_2") (pintype "passive"))
      (node (ref "SHIFT") (pin "4") (pinfunction "P1_4") (pintype "passive"))
    )
    (net (code "94") (name "VCC") (class "Default")
      (node (ref "C1") (pin "2") (pinfunction "2_2") (pintype "passive"))
      (node (ref "C2") (pin "1") (pinfunction "1_1") (pintype "passive"))
      (node (ref "C3") (pin "+") (pinfunction "+_+") (pintype "passive"))
      (node (ref "C4") (pin "1") (pinfunction "1_1") (pintype "passive"))
      (node (ref "C7") (pin "1") (pinfunction "1_1") (pintype "passive"))
      (node (ref "IC1") (pin "10") (pinfunction "VCC_10") (pintype "power_in"))
      (node (ref "IC1") (pin "30") (pinfunction "AVCC_30") (pintype "power_in"))
      (node (ref "Q1") (pin "E") (pinfunction "E_E") (pintype "passive"))
      (node (ref "Q2") (pin "E") (pinfunction "E_E") (pintype "passive"))
      (node (ref "Q3") (pin "E") (pinfunction "E_E") (pintype "passive"))
      (node (ref "Q4") (pin "E") (pinfunction "E_E") (pintype "passive"))
      (node (ref "Q5") (pin "E") (pinfunction "E_E") (pintype "passive"))
      (node (ref "Q6") (pin "E") (pinfunction "E_E") (pintype "passive"))
      (node (ref "Q7") (pin "E") (pinfunction "E_E") (pintype "passive"))
      (node (ref "Q8") (pin "E") (pinfunction "E_E") (pintype "passive"))
      (node (ref "R17") (pin "1") (pinfunction "1_1") (pintype "passive"))
      (node (ref "R26") (pin "1") (pinfunction "1_1") (pintype "passive"))
      (node (ref "R27") (pin "1") (pinfunction "1_1") (pintype "passive"))
      (node (ref "R28") (pin "1") (pinfunction "1_1") (pintype "passive"))
      (node (ref "R29") (pin "1") (pinfunction "1_1") (pintype "passive"))
      (node (ref "R30") (pin "1") (pinfunction "1_1") (pintype "passive"))
      (node (ref "R31") (pin "1") (pinfunction "1_1") (pintype "passive"))
      (node (ref "SL1") (pin "2") (pinfunction "2_2") (pintype "passive"))
      (node (ref "ULN1") (pin "10") (pinfunction "10_10") (pintype "bidirectional"))
      (node (ref "ULN2") (pin "10") (pinfunction "10_10") (pintype "bidirectional"))
    )
    (net (code "95") (name "unconnected-(INC_OR_DEC-P-Pad3)") (class "Default")
      (node (ref "INC_OR_DEC") (pin "3") (pinfunction "P_3") (pintype "passive"))
    )
    (net (code "96") (name "unconnected-(INC_OR_DEC-S1-Pad2)") (class "Default")
      (node (ref "INC_OR_DEC") (pin "2") (pinfunction "S1_2") (pintype "passive"))
    )
    (net (code "97") (name "unconnected-(LED1-C-Pad3)") (class "Default")
      (node (ref "LED1") (pin "3") (pinfunction "C_3") (pintype "passive"))
    )
    (net (code "98") (name "unconnected-(LED1-E-Pad4)") (class "Default")
      (node (ref "LED1") (pin "4") (pinfunction "E_4") (pintype "passive"))
    )
    (net (code "99") (name "unconnected-(LED2-C-Pad3)") (class "Default")
      (node (ref "LED2") (pin "3") (pinfunction "C_3") (pintype "passive"))
    )
    (net (code "100") (name "unconnected-(LED3-C-Pad3)") (class "Default")
      (node (ref "LED3") (pin "3") (pinfunction "C_3") (pintype "passive"))
    )
    (net (code "101") (name "unconnected-(LED4-C-Pad3)") (class "Default")
      (node (ref "LED4") (pin "3") (pinfunction "C_3") (pintype "passive"))
    )
    (net (code "102") (name "unconnected-(LED5-C-Pad3)") (class "Default")
      (node (ref "LED5") (pin "3") (pinfunction "C_3") (pintype "passive"))
    )
    (net (code "103") (name "unconnected-(LED6-C-Pad3)") (class "Default")
      (node (ref "LED6") (pin "3") (pinfunction "C_3") (pintype "passive"))
    )
    (net (code "104") (name "unconnected-(LED7-C-Pad3)") (class "Default")
      (node (ref "LED7") (pin "3") (pinfunction "C_3") (pintype "passive"))
    )
    (net (code "105") (name "unconnected-(LED8-C-Pad3)") (class "Default")
      (node (ref "LED8") (pin "3") (pinfunction "C_3") (pintype "passive"))
    )
    (net (code "106") (name "unconnected-(OK-P-Pad3)") (class "Default")
      (node (ref "OK") (pin "3") (pinfunction "P_3") (pintype "passive"))
    )
    (net (code "107") (name "unconnected-(OK-S1-Pad2)") (class "Default")
      (node (ref "OK") (pin "2") (pinfunction "S1_2") (pintype "passive"))
    )
    (net (code "108") (name "unconnected-(P1-P-Pad3)") (class "Default")
      (node (ref "P1") (pin "3") (pinfunction "P_3") (pintype "passive"))
    )
    (net (code "109") (name "unconnected-(P1-S1-Pad2)") (class "Default")
      (node (ref "P1") (pin "2") (pinfunction "S1_2") (pintype "passive"))
    )
    (net (code "110") (name "unconnected-(P2-P-Pad3)") (class "Default")
      (node (ref "P2") (pin "3") (pinfunction "P_3") (pintype "passive"))
    )
    (net (code "111") (name "unconnected-(P2-S1-Pad2)") (class "Default")
      (node (ref "P2") (pin "2") (pinfunction "S1_2") (pintype "passive"))
    )
    (net (code "112") (name "unconnected-(PAUSE-P-Pad3)") (class "Default")
      (node (ref "PAUSE") (pin "3") (pinfunction "P_3") (pintype "passive"))
    )
    (net (code "113") (name "unconnected-(PAUSE-S1-Pad2)") (class "Default")
      (node (ref "PAUSE") (pin "2") (pinfunction "S1_2") (pintype "passive"))
    )
    (net (code "114") (name "unconnected-(SHIFT-P-Pad3)") (class "Default")
      (node (ref "SHIFT") (pin "3") (pinfunction "P_3") (pintype "passive"))
    )
    (net (code "115") (name "unconnected-(SHIFT-S1-Pad2)") (class "Default")
      (node (ref "SHIFT") (pin "2") (pinfunction "S1_2") (pintype "passive"))
    )
    (net (code "116") (name "unconnected-(SHIFT1-P1-Pad4)") (class "Default")
      (node (ref "SHIFT1") (pin "4") (pinfunction "P1_4") (pintype "passive"))
    )
    (net (code "117") (name "unconnected-(SHIFT1-S1-Pad2)") (class "Default")
      (node (ref "SHIFT1") (pin "2") (pinfunction "S1_2") (pintype "passive"))
    )
  )
)
